# USB.net
KiCad netlist of a schematic drawn in Altium Designer
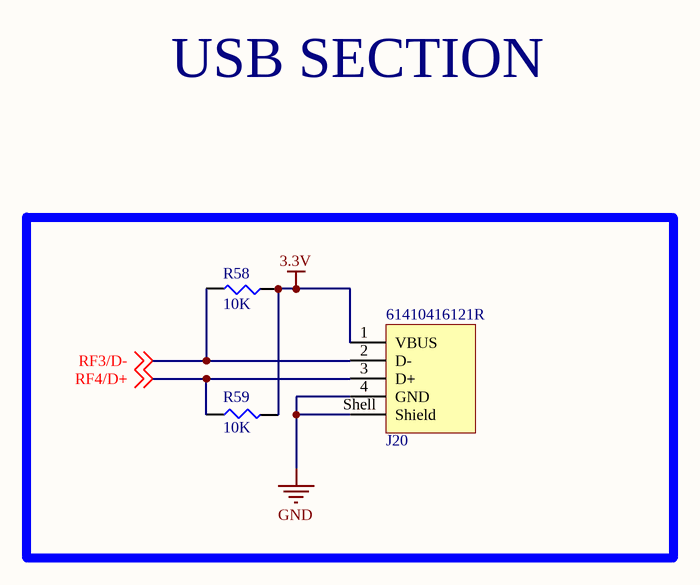
[diagram p0: USB.SchDoc]

(export (version "E")
  (design (tool "Eeschema 10.0.6"))
  (components
    (comp (ref "J20")
      (value "61410416121R")
      (footprint "61410416121R")
      (description "WR-COM USB 2.0 Type B Horizontal THR")
      (fields (field (name "MANUFACTURER") "Wurth Elektronik"))
      (libsource (lib "Altium_WR-USB (rev23b)") (part "61410416121R"))
    )
    (comp (ref "R58")
      (value "10K")
      (footprint "SMD-0805-RES")
      (description "RES SMD 1K OHM 1% 1/8W 0805")
      (fields
        (field (name "PART NUMBER") "ERJ-6ENF1001V")
        (field (name "DIGI-KEY PART NUMBER") "P1.00KCCT-ND")
      )
      (libsource (lib "Panasonic_ERJ_0805") (part "ERJ-6ENF1001V"))
    )
    (comp (ref "R59")
      (value "10K")
      (footprint "SMD-0805-RES")
      (description "RES SMD 1K OHM 1% 1/8W 0805")
      (fields
        (field (name "PART NUMBER") "ERJ-6ENF1001V")
        (field (name "DIGI-KEY PART NUMBER") "P1.00KCCT-ND")
      )
      (libsource (lib "Panasonic_ERJ_0805") (part "ERJ-6ENF1001V"))
    )
  )
  (nets
    (net (code "1") (name "3.3V") (class "Default")
      (node (ref "J20") (pin "1") (pinfunction "VBUS_1") (pintype "passive"))
      (node (ref "R58") (pin "1") (pinfunction "1_1") (pintype "passive"))
      (node (ref "R59") (pin "2") (pinfunction "2_2") (pintype "passive"))
    )
    (net (code "2") (name "GND") (class "Default")
      (node (ref "J20") (pin "4") (pinfunction "GND_4") (pintype "passive"))
      (node (ref "J20") (pin "Shell") (pinfunction "Shield_Shell") (pintype "passive"))
    )
    (net (code "3") (name "RF3{slash}D-") (class "Default")
      (node (ref "J20") (pin "2") (pinfunction "D-_2") (pintype "passive"))
      (node (ref "R58") (pin "2") (pinfunction "2_2") (pintype "passive"))
    )
    (net (code "4") (name "RF4{slash}D+") (class "Default")
      (node (ref "J20") (pin "3") (pinfunction "D+_3") (pintype "passive"))
      (node (ref "R59") (pin "1") (pinfunction "1_1") (pintype "passive"))
    )
  )
)
